# SCH_BUTTON.net
KiCad netlist of a schematic drawn in Altium Designer
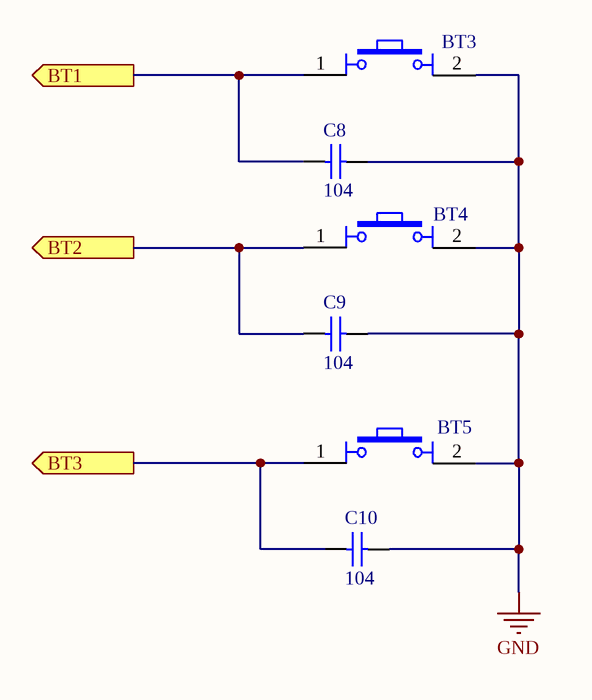
[diagram p0: SCH_BUTTON.SchDoc]

(export (version "E")
  (design (tool "Eeschema 10.0.6"))
  (components
    (comp (ref "BT3")
      (value "~")
      (footprint "Nut Nhan 4 Chan Cam 6x6")
      (description "Nut Nhan 4 Chan 6x6mm")
      (libsource (lib "Altium_Lib_by_KhueNguyenCreator") (part "Nut Nhan 4 Chan Cam 6x6"))
    )
    (comp (ref "BT4")
      (value "~")
      (footprint "Nut Nhan 4 Chan Cam 6x6")
      (description "Nut Nhan 4 Chan 6x6mm")
      (libsource (lib "Altium_Lib_by_KhueNguyenCreator") (part "Nut Nhan 4 Chan Cam 6x6"))
    )
    (comp (ref "BT5")
      (value "~")
      (footprint "Nut Nhan 4 Chan Cam 6x6")
      (description "Nut Nhan 4 Chan 6x6mm")
      (libsource (lib "Altium_Lib_by_KhueNguyenCreator") (part "Nut Nhan 4 Chan Cam 6x6"))
    )
    (comp (ref "C8")
      (value "104")
      (footprint "tu 0805")
      (description "Dán")
      (libsource (lib "Altium_Lib_by_KhueNguyenCreator") (part "Tu 0805 104 50V 10%"))
    )
    (comp (ref "C9")
      (value "104")
      (footprint "tu 0805")
      (description "Dán")
      (libsource (lib "Altium_Lib_by_KhueNguyenCreator") (part "Tu 0805 104 50V 10%"))
    )
    (comp (ref "C10")
      (value "104")
      (footprint "tu 0805")
      (description "Dán")
      (libsource (lib "Altium_Lib_by_KhueNguyenCreator") (part "Tu 0805 104 50V 10%"))
    )
  )
  (nets
    (net (code "1") (name "/BT1") (class "Default")
      (node (ref "BT3") (pin "1") (pintype "passive"))
      (node (ref "C8") (pin "1") (pinfunction "1_1") (pintype "passive"))
    )
    (net (code "2") (name "/BT2") (class "Default")
      (node (ref "BT4") (pin "1") (pintype "passive"))
      (node (ref "C9") (pin "1") (pinfunction "1_1") (pintype "passive"))
    )
    (net (code "3") (name "/BT3") (class "Default")
      (node (ref "BT5") (pin "1") (pintype "passive"))
      (node (ref "C10") (pin "1") (pinfunction "1_1") (pintype "passive"))
    )
    (net (code "4") (name "GND") (class "Default")
      (node (ref "BT3") (pin "2") (pintype "passive"))
      (node (ref "BT4") (pin "2") (pintype "passive"))
      (node (ref "BT5") (pin "2") (pintype "passive"))
      (node (ref "C10") (pin "2") (pinfunction "2_2") (pintype "passive"))
      (node (ref "C8") (pin "2") (pinfunction "2_2") (pintype "passive"))
      (node (ref "C9") (pin "2") (pinfunction "2_2") (pintype "passive"))
    )
  )
)
